# ECG.net
KiCad netlist of a schematic drawn in Altium Designer
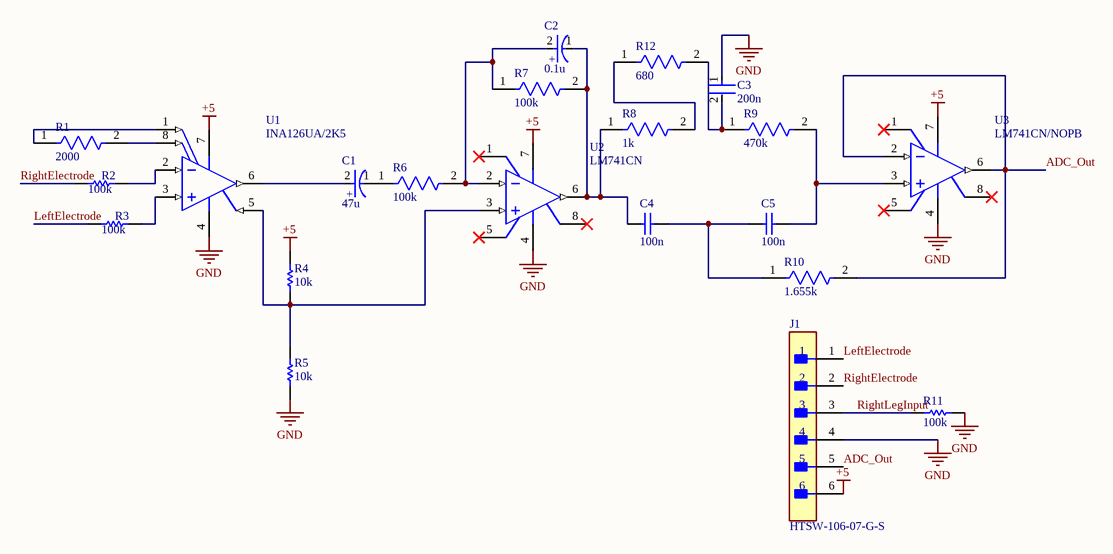
[diagram p0: ECG.SchDoc]

(export (version "E")
  (design (tool "Eeschema 10.0.6"))
  (components
    (comp (ref "C1")
      (value "47u")
      (footprint "FP-RAD-TH-D_8_0_5-L_20_2-MFG")
      (description "Aluminum Electrolytic Capacitors (Radial Lead Type) AEC-Q200 Qualified 270uF ±20% 35V")
      (libsource (lib "Altium Content Vault") (part "203bc49f2ac43e59fd269a8c329ed05"))
    )
    (comp (ref "C2")
      (value "0.1u")
      (footprint "FP-RAD-TH-D_8_0_5-L_20_2-MFG")
      (description "Aluminum Electrolytic Capacitors (Radial Lead Type) AEC-Q200 Qualified 270uF ±20% 35V")
      (libsource (lib "Altium Content Vault") (part "203bc49f2ac43e59fd269a8c329ed05"))
    )
    (comp (ref "C3")
      (value "200n")
      (footprint "FP-R82DC4100DQ60J-MFG")
      (description "CAP FILM 1UF 5% 63VDC RADIAL")
      (fields (field (name "VOLTAGE") "63V") (field (name "TOLERANCE") "5%"))
      (libsource (lib "Altium Content Vault") (part "11868f565c42a9108669ba33697ecf6"))
    )
    (comp (ref "C4")
      (value "100n")
      (footprint "CAPR51-254-508X318X736")
      (libsource (lib "Altium Content Vault") (part "CAP-NP-2"))
    )
    (comp (ref "C5")
      (value "100n")
      (footprint "CAPR51-254-508X318X736")
      (libsource (lib "Altium Content Vault") (part "CAP-NP-2"))
    )
    (comp (ref "J1")
      (value "HTSW-106-07-G-S")
      (footprint "FP-HTSW-106-07-G-S-MFG")
      (description "CONN HEADER VERT 6POS 2.54MM")
      (libsource (lib "Altium Content Vault") (part "f2cb566baf1c37ab5a3b8e90bbeafd6"))
    )
    (comp (ref "R1")
      (value "2000")
      (footprint "FP-MRS25-MFG")
      (fields (field (name "TOLERANCE") "1%"))
      (libsource (lib "Altium Content Vault") (part "1029c3af85768c4190bb7ad29bc67b5"))
    )
    (comp (ref "R2")
      (value "100k")
      (footprint "6-0805_N")
      (description "Resistor")
      (fields
        (field (name "POWER") "125mW")
        (field (name "Comment") "Res 0805")
        (field (name "PUBLISHER") "Altium Limited")
      )
      (libsource (lib "Supermileage Vehicle at UCLA") (part "Res1_4"))
    )
    (comp (ref "R3")
      (value "100k")
      (footprint "6-0805_N")
      (description "Resistor")
      (fields
        (field (name "POWER") "125mW")
        (field (name "Comment") "Res 0805")
        (field (name "PUBLISHER") "Altium Limited")
      )
      (libsource (lib "Supermileage Vehicle at UCLA") (part "Res1_4"))
    )
    (comp (ref "R4")
      (value "10k")
      (footprint "6-0805_N")
      (description "Resistor")
      (fields
        (field (name "POWER") "125mW")
        (field (name "Comment") "Res 0805")
        (field (name "PUBLISHER") "Altium Limited")
      )
      (libsource (lib "Supermileage Vehicle at UCLA") (part "Res1_4"))
    )
    (comp (ref "R5")
      (value "10k")
      (footprint "6-0805_N")
      (description "Resistor")
      (fields
        (field (name "POWER") "125mW")
        (field (name "Comment") "Res 0805")
        (field (name "PUBLISHER") "Altium Limited")
      )
      (libsource (lib "Supermileage Vehicle at UCLA") (part "Res1_4"))
    )
    (comp (ref "R6")
      (value "100k")
      (footprint "FP-MRS25-MFG")
      (fields (field (name "TOLERANCE") "1%"))
      (libsource (lib "Altium Content Vault") (part "1029c3af85768c4190bb7ad29bc67b5"))
    )
    (comp (ref "R7")
      (value "100k")
      (footprint "FP-MRS25-MFG")
      (fields (field (name "TOLERANCE") "1%"))
      (libsource (lib "Altium Content Vault") (part "1029c3af85768c4190bb7ad29bc67b5"))
    )
    (comp (ref "R8")
      (value "1k")
      (footprint "FP-MRS25-MFG")
      (fields (field (name "TOLERANCE") "1%"))
      (libsource (lib "Altium Content Vault") (part "1029c3af85768c4190bb7ad29bc67b5"))
    )
    (comp (ref "R9")
      (value "470k")
      (footprint "FP-MRS25-MFG")
      (fields (field (name "TOLERANCE") "1%"))
      (libsource (lib "Altium Content Vault") (part "1029c3af85768c4190bb7ad29bc67b5"))
    )
    (comp (ref "R10")
      (value "1.655k")
      (footprint "FP-MRS25-MFG")
      (fields (field (name "TOLERANCE") "1%"))
      (libsource (lib "Altium Content Vault") (part "1029c3af85768c4190bb7ad29bc67b5"))
    )
    (comp (ref "R11")
      (value "100k")
      (footprint "6-0805_N")
      (description "Resistor")
      (fields
        (field (name "POWER") "125mW")
        (field (name "Comment") "Res 0805")
        (field (name "PUBLISHER") "Altium Limited")
      )
      (libsource (lib "Supermileage Vehicle at UCLA") (part "Res1_4"))
    )
    (comp (ref "R12")
      (value "680")
      (footprint "FP-MRS25-MFG")
      (fields (field (name "TOLERANCE") "1%"))
      (libsource (lib "Altium Content Vault") (part "1029c3af85768c4190bb7ad29bc67b5"))
    )
    (comp (ref "U1")
      (value "INA126UA/2K5")
      (footprint "D0008A_N")
      (fields (field (name "MANUFACTURER") "Texas Instruments"))
      (libsource (lib "Altium Content Vault") (part "TI-INA1XX-8"))
    )
    (comp (ref "U2")
      (value "LM741CN")
      (footprint "P0008A")
      (description "Operational Amplifier, 8-pin MDIP, Pb-Free")
      (fields (field (name "MANUFACTURER") "Texas Instruments"))
      (libsource (lib "Altium Content Vault") (part "AMP-OPA-LM741-8"))
    )
    (comp (ref "U3")
      (value "LM741CN/NOPB")
      (footprint "P0008A")
      (description "Operational Amplifier, 8-pin MDIP, Pb-Free")
      (fields (field (name "MANUFACTURER") "Texas Instruments"))
      (libsource (lib "Altium Content Vault") (part "AMP-OPA-LM741-8"))
    )
  )
  (nets
    (net (code "1") (name "+5") (class "Default")
      (node (ref "J1") (pin "6") (pinfunction "6_6") (pintype "passive"))
      (node (ref "R4") (pin "2") (pinfunction "2_2") (pintype "passive"))
      (node (ref "U1") (pin "7") (pinfunction "V+_7") (pintype "power_in"))
      (node (ref "U2") (pin "7") (pinfunction "V+_7") (pintype "power_in"))
      (node (ref "U3") (pin "7") (pinfunction "V+_7") (pintype "power_in"))
    )
    (net (code "2") (name "/ADC_Out") (class "Default")
      (node (ref "J1") (pin "5") (pinfunction "5_5") (pintype "passive"))
      (node (ref "R10") (pin "2") (pinfunction "2_2") (pintype "passive"))
      (node (ref "U3") (pin "2") (pinfunction "IN-_2") (pintype "input"))
      (node (ref "U3") (pin "6") (pinfunction "OUT_6") (pintype "output"))
    )
    (net (code "3") (name "/LeftElectrode") (class "Default")
      (node (ref "J1") (pin "1") (pinfunction "1_1") (pintype "passive"))
      (node (ref "R3") (pin "1") (pinfunction "1_1") (pintype "passive"))
    )
    (net (code "4") (name "/RightElectrode") (class "Default")
      (node (ref "J1") (pin "2") (pinfunction "2_2") (pintype "passive"))
      (node (ref "R2") (pin "1") (pinfunction "1_1") (pintype "passive"))
    )
    (net (code "5") (name "/RightLegInput") (class "Default")
      (node (ref "J1") (pin "3") (pinfunction "3_3") (pintype "passive"))
      (node (ref "R11") (pin "1") (pinfunction "1_1") (pintype "passive"))
    )
    (net (code "6") (name "GND") (class "Default")
      (node (ref "C3") (pin "1") (pinfunction "1_1") (pintype "passive"))
      (node (ref "J1") (pin "4") (pinfunction "4_4") (pintype "passive"))
      (node (ref "R11") (pin "2") (pinfunction "2_2") (pintype "passive"))
      (node (ref "R5") (pin "1") (pinfunction "1_1") (pintype "passive"))
      (node (ref "U1") (pin "4") (pinfunction "V-_4") (pintype "power_in"))
      (node (ref "U2") (pin "4") (pinfunction "V-_4") (pintype "power_in"))
      (node (ref "U3") (pin "4") (pinfunction "V-_4") (pintype "power_in"))
    )
    (net (code "7") (name "Net-(C1-A)") (class "Default")
      (node (ref "C1") (pin "2") (pinfunction "A_2") (pintype "passive"))
      (node (ref "U1") (pin "6") (pinfunction "VO_6") (pintype "output"))
    )
    (net (code "8") (name "Net-(C1-C)") (class "Default")
      (node (ref "C1") (pin "1") (pinfunction "C_1") (pintype "passive"))
      (node (ref "R6") (pin "1") (pinfunction "1_1") (pintype "passive"))
    )
    (net (code "9") (name "Net-(C2-A)") (class "Default")
      (node (ref "C2") (pin "2") (pinfunction "A_2") (pintype "passive"))
      (node (ref "R6") (pin "2") (pinfunction "2_2") (pintype "passive"))
      (node (ref "R7") (pin "1") (pinfunction "1_1") (pintype "passive"))
      (node (ref "U2") (pin "2") (pinfunction "IN-_2") (pintype "input"))
    )
    (net (code "10") (name "Net-(C2-C)") (class "Default")
      (node (ref "C2") (pin "1") (pinfunction "C_1") (pintype "passive"))
      (node (ref "C4") (pin "1") (pinfunction "1_1") (pintype "passive"))
      (node (ref "R7") (pin "2") (pinfunction "2_2") (pintype "passive"))
      (node (ref "R8") (pin "1") (pinfunction "1_1") (pintype "passive"))
      (node (ref "U2") (pin "6") (pinfunction "OUT_6") (pintype "output"))
    )
    (net (code "11") (name "Net-(C3-Pad2)") (class "Default")
      (node (ref "C3") (pin "2") (pinfunction "2_2") (pintype "passive"))
      (node (ref "R12") (pin "2") (pinfunction "2_2") (pintype "passive"))
      (node (ref "R9") (pin "1") (pinfunction "1_1") (pintype "passive"))
    )
    (net (code "12") (name "Net-(C4-Pad2)") (class "Default")
      (node (ref "C4") (pin "2") (pinfunction "2_2") (pintype "passive"))
      (node (ref "C5") (pin "1") (pinfunction "1_1") (pintype "passive"))
      (node (ref "R10") (pin "1") (pinfunction "1_1") (pintype "passive"))
    )
    (net (code "13") (name "Net-(R1-Pad1)") (class "Default")
      (node (ref "R1") (pin "1") (pinfunction "1_1") (pintype "passive"))
      (node (ref "U1") (pin "1") (pinfunction "RG_1") (pintype "input"))
    )
    (net (code "14") (name "Net-(R1-Pad2)") (class "Default")
      (node (ref "R1") (pin "2") (pinfunction "2_2") (pintype "passive"))
      (node (ref "U1") (pin "8") (pinfunction "RG_8") (pintype "input"))
    )
    (net (code "15") (name "Net-(R12-Pad1)") (class "Default")
      (node (ref "R12") (pin "1") (pinfunction "1_1") (pintype "passive"))
      (node (ref "R8") (pin "2") (pinfunction "2_2") (pintype "passive"))
    )
    (net (code "16") (name "Net-(U1-REF)") (class "Default")
      (node (ref "R4") (pin "1") (pinfunction "1_1") (pintype "passive"))
      (node (ref "R5") (pin "2") (pinfunction "2_2") (pintype "passive"))
      (node (ref "U1") (pin "5") (pinfunction "REF_5") (pintype "input"))
      (node (ref "U2") (pin "3") (pinfunction "IN+_3") (pintype "input"))
    )
    (net (code "17") (name "Net-(U1-VIN+)") (class "Default")
      (node (ref "R3") (pin "2") (pinfunction "2_2") (pintype "passive"))
      (node (ref "U1") (pin "3") (pinfunction "VIN+_3") (pintype "input"))
    )
    (net (code "18") (name "Net-(U1-VIN-)") (class "Default")
      (node (ref "R2") (pin "2") (pinfunction "2_2") (pintype "passive"))
      (node (ref "U1") (pin "2") (pinfunction "VIN-_2") (pintype "input"))
    )
    (net (code "19") (name "Net-(U3-IN+)") (class "Default")
      (node (ref "C5") (pin "2") (pinfunction "2_2") (pintype "passive"))
      (node (ref "R9") (pin "2") (pinfunction "2_2") (pintype "passive"))
      (node (ref "U3") (pin "3") (pinfunction "IN+_3") (pintype "input"))
    )
    (net (code "20") (name "unconnected-(U2-NC-Pad8)") (class "Default")
      (node (ref "U2") (pin "8") (pinfunction "NC_8") (pintype "passive+no_connect"))
    )
    (net (code "21") (name "unconnected-(U2-OFS_NULL-Pad1)") (class "Default")
      (node (ref "U2") (pin "1") (pinfunction "OFS_NULL_1") (pintype "passive+no_connect"))
    )
    (net (code "22") (name "unconnected-(U2-OFS_NULL-Pad5)") (class "Default")
      (node (ref "U2") (pin "5") (pinfunction "OFS_NULL_5") (pintype "passive+no_connect"))
    )
    (net (code "23") (name "unconnected-(U3-NC-Pad8)") (class "Default")
      (node (ref "U3") (pin "8") (pinfunction "NC_8") (pintype "passive+no_connect"))
    )
    (net (code "24") (name "unconnected-(U3-OFS_NULL-Pad1)") (class "Default")
      (node (ref "U3") (pin "1") (pinfunction "OFS_NULL_1") (pintype "passive+no_connect"))
    )
    (net (code "25") (name "unconnected-(U3-OFS_NULL-Pad5)") (class "Default")
      (node (ref "U3") (pin "5") (pinfunction "OFS_NULL_5") (pintype "passive+no_connect"))
    )
  )
)
